# c1101_atmega32u4.net
KiCad netlist of a schematic drawn in EAGLE
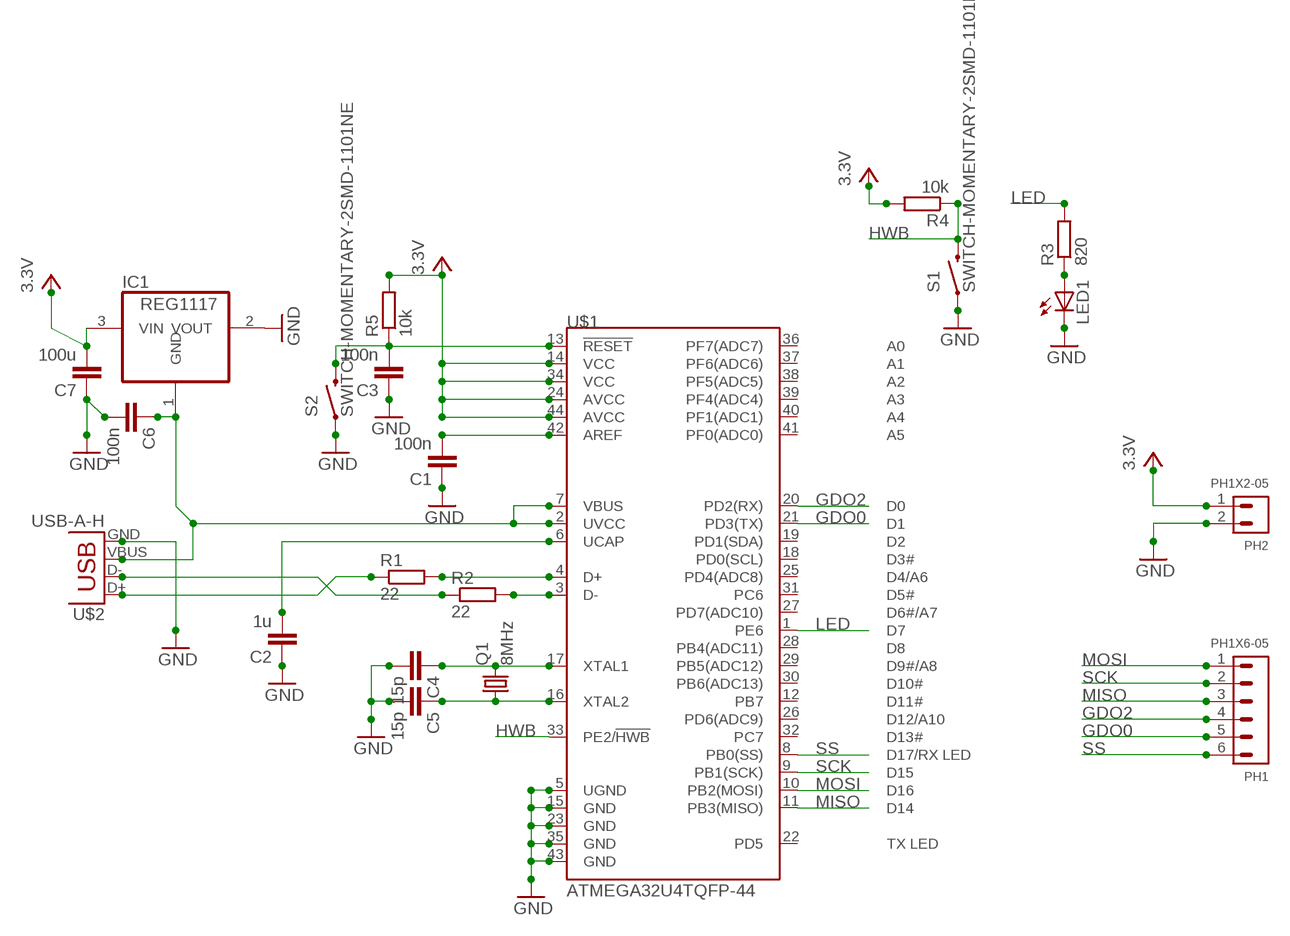
[diagram p0: schematic, sheet 1]

(export (version "E")
  (design (tool "Eeschema 10.0.6"))
  (components
    (comp (ref "C1")
      (value "100n")
      (footprint "eagle-import:C0805")
      (libsource (lib "eagle-import") (part "C-EUC0805"))
    )
    (comp (ref "C2")
      (value "1u")
      (footprint "eagle-import:C0805")
      (libsource (lib "eagle-import") (part "C-EUC0805"))
    )
    (comp (ref "C3")
      (value "100n")
      (footprint "eagle-import:C0805")
      (libsource (lib "eagle-import") (part "C-EUC0805"))
    )
    (comp (ref "C4")
      (value "15p")
      (footprint "eagle-import:C0805")
      (libsource (lib "eagle-import") (part "C-EUC0805"))
    )
    (comp (ref "C5")
      (value "15p")
      (footprint "eagle-import:C0805")
      (libsource (lib "eagle-import") (part "C-EUC0805"))
    )
    (comp (ref "C6")
      (value "100n")
      (footprint "eagle-import:C0805")
      (libsource (lib "eagle-import") (part "C-EUC0805"))
    )
    (comp (ref "C7")
      (value "100u")
      (footprint "eagle-import:C0805")
      (libsource (lib "eagle-import") (part "C-EUC0805"))
    )
    (comp (ref "IC1")
      (value "REG1117")
      (footprint "eagle-import:SOT223")
      (libsource (lib "eagle-import") (part "REG1117"))
    )
    (comp (ref "LED1")
      (value "LEDCHIPLED_1206")
      (footprint "eagle-import:CHIPLED_1206")
      (libsource (lib "eagle-import") (part "LEDCHIPLED_1206"))
    )
    (comp (ref "PH1")
      (value "PH1X6-05")
      (footprint "eagle-import:PH005-1-6")
      (libsource (lib "eagle-import") (part "PH1X6-05"))
    )
    (comp (ref "PH2")
      (value "PH1X2-05")
      (footprint "eagle-import:PH005-1-2")
      (libsource (lib "eagle-import") (part "PH1X2-05"))
    )
    (comp (ref "Q1")
      (value "8MHz")
      (footprint "eagle-import:HC49_S")
      (libsource (lib "eagle-import") (part "CRYSTALHC49S"))
    )
    (comp (ref "R1")
      (value "22")
      (footprint "eagle-import:M0805")
      (libsource (lib "eagle-import") (part "R-EU_M0805"))
    )
    (comp (ref "R2")
      (value "22")
      (footprint "eagle-import:M0805")
      (libsource (lib "eagle-import") (part "R-EU_M0805"))
    )
    (comp (ref "R3")
      (value "820")
      (footprint "eagle-import:M0805")
      (libsource (lib "eagle-import") (part "R-EU_M0805"))
    )
    (comp (ref "R4")
      (value "10k")
      (footprint "eagle-import:M0805")
      (libsource (lib "eagle-import") (part "R-EU_M0805"))
    )
    (comp (ref "R5")
      (value "10k")
      (footprint "eagle-import:M0805")
      (libsource (lib "eagle-import") (part "R-EU_M0805"))
    )
    (comp (ref "S1")
      (value "SWITCH-MOMENTARY-2SMD-1101NE")
      (footprint "eagle-import:TACTILE-SWITCH-1101NE")
      (libsource (lib "eagle-import") (part "SWITCH-MOMENTARY-2SMD-1101NE"))
    )
    (comp (ref "S2")
      (value "SWITCH-MOMENTARY-2SMD-1101NE")
      (footprint "eagle-import:TACTILE-SWITCH-1101NE")
      (libsource (lib "eagle-import") (part "SWITCH-MOMENTARY-2SMD-1101NE"))
    )
    (comp (ref "U$1")
      (value "ATMEGA32U4TQFP-44")
      (footprint "eagle-import:TQFP44")
      (libsource (lib "eagle-import") (part "ATMEGA32U4TQFP-44"))
    )
    (comp (ref "U$2")
      (value "USB-A-H")
      (footprint "eagle-import:USB-A-H")
      (libsource (lib "eagle-import") (part "USB-A-H"))
    )
  )
  (nets
    (net (code "1") (name "/GDO0") (class "Default")
      (node (ref "PH1") (pin "5") (pinfunction "5_5") (pintype "bidirectional"))
      (node (ref "U$1") (pin "21") (pinfunction "PD3(TX)_21") (pintype "bidirectional"))
    )
    (net (code "2") (name "/GDO2") (class "Default")
      (node (ref "PH1") (pin "4") (pinfunction "4_4") (pintype "bidirectional"))
      (node (ref "U$1") (pin "20") (pinfunction "PD2(RX)_20") (pintype "bidirectional"))
    )
    (net (code "3") (name "/HWB") (class "Default")
      (node (ref "R4") (pin "1") (pinfunction "1_1") (pintype "passive"))
      (node (ref "S1") (pin "2") (pinfunction "2_2") (pintype "passive"))
      (node (ref "U$1") (pin "33") (pinfunction "PE2/~{HWB}_33") (pintype "bidirectional"))
    )
    (net (code "4") (name "/LED") (class "Default")
      (node (ref "R3") (pin "2") (pinfunction "2_2") (pintype "passive"))
      (node (ref "U$1") (pin "1") (pinfunction "PE6_1") (pintype "bidirectional"))
    )
    (net (code "5") (name "/MISO") (class "Default")
      (node (ref "PH1") (pin "3") (pinfunction "3_3") (pintype "bidirectional"))
      (node (ref "U$1") (pin "11") (pinfunction "PB3(MISO)_11") (pintype "bidirectional"))
    )
    (net (code "6") (name "/MOSI") (class "Default")
      (node (ref "PH1") (pin "1") (pinfunction "1_1") (pintype "bidirectional"))
      (node (ref "U$1") (pin "10") (pinfunction "PB2(MOSI)_10") (pintype "bidirectional"))
    )
    (net (code "7") (name "/SCK") (class "Default")
      (node (ref "PH1") (pin "2") (pinfunction "2_2") (pintype "bidirectional"))
      (node (ref "U$1") (pin "9") (pinfunction "PB1(SCK)_9") (pintype "bidirectional"))
    )
    (net (code "8") (name "/SS") (class "Default")
      (node (ref "PH1") (pin "6") (pinfunction "6_6") (pintype "bidirectional"))
      (node (ref "U$1") (pin "8") (pinfunction "PB0(SS)_8") (pintype "bidirectional"))
    )
    (net (code "9") (name "3.3V") (class "Default")
      (node (ref "C7") (pin "2") (pinfunction "2_2") (pintype "passive"))
      (node (ref "IC1") (pin "3") (pinfunction "VIN_3") (pintype "input"))
      (node (ref "PH2") (pin "1") (pinfunction "1_1") (pintype "bidirectional"))
      (node (ref "R4") (pin "2") (pinfunction "2_2") (pintype "passive"))
      (node (ref "R5") (pin "2") (pinfunction "2_2") (pintype "passive"))
      (node (ref "U$1") (pin "14") (pinfunction "VCC_14") (pintype "bidirectional"))
      (node (ref "U$1") (pin "24") (pinfunction "AVCC_24") (pintype "bidirectional"))
      (node (ref "U$1") (pin "34") (pinfunction "VCC_34") (pintype "bidirectional"))
      (node (ref "U$1") (pin "44") (pinfunction "AVCC_44") (pintype "bidirectional"))
    )
    (net (code "10") (name "GND") (class "Default")
      (node (ref "C1") (pin "1") (pinfunction "1_1") (pintype "passive"))
      (node (ref "C2") (pin "1") (pinfunction "1_1") (pintype "passive"))
      (node (ref "C3") (pin "1") (pinfunction "1_1") (pintype "passive"))
      (node (ref "C4") (pin "2") (pinfunction "2_2") (pintype "passive"))
      (node (ref "C5") (pin "2") (pinfunction "2_2") (pintype "passive"))
      (node (ref "C6") (pin "2") (pinfunction "2_2") (pintype "passive"))
      (node (ref "C7") (pin "1") (pinfunction "1_1") (pintype "passive"))
      (node (ref "IC1") (pin "2") (pinfunction "VOUT_2") (pintype "output"))
      (node (ref "LED1") (pin "C") (pinfunction "C_C") (pintype "passive"))
      (node (ref "PH2") (pin "2") (pinfunction "2_2") (pintype "bidirectional"))
      (node (ref "S1") (pin "1") (pinfunction "1_1") (pintype "passive"))
      (node (ref "S2") (pin "1") (pinfunction "1_1") (pintype "passive"))
      (node (ref "U$1") (pin "15") (pinfunction "GND_15") (pintype "bidirectional"))
      (node (ref "U$1") (pin "23") (pinfunction "GND_23") (pintype "bidirectional"))
      (node (ref "U$1") (pin "35") (pinfunction "GND_35") (pintype "bidirectional"))
      (node (ref "U$1") (pin "43") (pinfunction "GND_43") (pintype "bidirectional"))
      (node (ref "U$1") (pin "5") (pinfunction "UGND_5") (pintype "bidirectional"))
      (node (ref "U$2") (pin "GND") (pinfunction "GND_GND") (pintype "bidirectional"))
    )
    (net (code "11") (name "Net-(IC1-GND)") (class "Default")
      (node (ref "C6") (pin "1") (pinfunction "1_1") (pintype "passive"))
      (node (ref "IC1") (pin "1") (pinfunction "GND_1") (pintype "power_in"))
      (node (ref "U$1") (pin "2") (pinfunction "UVCC_2") (pintype "bidirectional"))
      (node (ref "U$1") (pin "7") (pinfunction "VBUS_7") (pintype "bidirectional"))
      (node (ref "U$2") (pin "VBUS") (pinfunction "VBUS_VBUS") (pintype "bidirectional"))
    )
    (net (code "12") (name "Net-(LED1-PadA)") (class "Default")
      (node (ref "LED1") (pin "A") (pinfunction "A_A") (pintype "passive"))
      (node (ref "R3") (pin "1") (pinfunction "1_1") (pintype "passive"))
    )
    (net (code "13") (name "Net-(R1-Pad1)") (class "Default")
      (node (ref "R1") (pin "1") (pinfunction "1_1") (pintype "passive"))
      (node (ref "U$2") (pin "D+") (pinfunction "D+_D+") (pintype "bidirectional"))
    )
    (net (code "14") (name "Net-(R2-Pad1)") (class "Default")
      (node (ref "R2") (pin "1") (pinfunction "1_1") (pintype "passive"))
      (node (ref "U$2") (pin "D-") (pinfunction "D-_D-") (pintype "bidirectional"))
    )
    (net (code "15") (name "Net-(U$1-AREF)") (class "Default")
      (node (ref "C1") (pin "2") (pinfunction "2_2") (pintype "passive"))
      (node (ref "U$1") (pin "42") (pinfunction "AREF_42") (pintype "bidirectional"))
    )
    (net (code "16") (name "Net-(U$1-D+)") (class "Default")
      (node (ref "R1") (pin "2") (pinfunction "2_2") (pintype "passive"))
      (node (ref "U$1") (pin "4") (pinfunction "D+_4") (pintype "bidirectional"))
    )
    (net (code "17") (name "Net-(U$1-D-)") (class "Default")
      (node (ref "R2") (pin "2") (pinfunction "2_2") (pintype "passive"))
      (node (ref "U$1") (pin "3") (pinfunction "D-_3") (pintype "bidirectional"))
    )
    (net (code "18") (name "Net-(U$1-UCAP)") (class "Default")
      (node (ref "C2") (pin "2") (pinfunction "2_2") (pintype "passive"))
      (node (ref "U$1") (pin "6") (pinfunction "UCAP_6") (pintype "bidirectional"))
    )
    (net (code "19") (name "Net-(U$1-XTAL1)") (class "Default")
      (node (ref "C4") (pin "1") (pinfunction "1_1") (pintype "passive"))
      (node (ref "Q1") (pin "2") (pinfunction "2_2") (pintype "passive"))
      (node (ref "U$1") (pin "17") (pinfunction "XTAL1_17") (pintype "bidirectional"))
    )
    (net (code "20") (name "Net-(U$1-XTAL2)") (class "Default")
      (node (ref "C5") (pin "1") (pinfunction "1_1") (pintype "passive"))
      (node (ref "Q1") (pin "1") (pinfunction "1_1") (pintype "passive"))
      (node (ref "U$1") (pin "16") (pinfunction "XTAL2_16") (pintype "bidirectional"))
    )
    (net (code "21") (name "Net-(U$1-~{RESET})") (class "Default")
      (node (ref "C3") (pin "2") (pinfunction "2_2") (pintype "passive"))
      (node (ref "R5") (pin "1") (pinfunction "1_1") (pintype "passive"))
      (node (ref "S2") (pin "2") (pinfunction "2_2") (pintype "passive"))
      (node (ref "U$1") (pin "13") (pinfunction "~{RESET}_13") (pintype "bidirectional"))
    )
    (net (code "22") (name "unconnected-(U$1-PB4(ADC11)-Pad28)") (class "Default")
      (node (ref "U$1") (pin "28") (pinfunction "PB4(ADC11)_28") (pintype "bidirectional"))
    )
    (net (code "23") (name "unconnected-(U$1-PB5(ADC12)-Pad29)") (class "Default")
      (node (ref "U$1") (pin "29") (pinfunction "PB5(ADC12)_29") (pintype "bidirectional"))
    )
    (net (code "24") (name "unconnected-(U$1-PB6(ADC13)-Pad30)") (class "Default")
      (node (ref "U$1") (pin "30") (pinfunction "PB6(ADC13)_30") (pintype "bidirectional"))
    )
    (net (code "25") (name "unconnected-(U$1-PB7-Pad12)") (class "Default")
      (node (ref "U$1") (pin "12") (pinfunction "PB7_12") (pintype "bidirectional"))
    )
    (net (code "26") (name "unconnected-(U$1-PC6-Pad31)") (class "Default")
      (node (ref "U$1") (pin "31") (pinfunction "PC6_31") (pintype "bidirectional"))
    )
    (net (code "27") (name "unconnected-(U$1-PC7-Pad32)") (class "Default")
      (node (ref "U$1") (pin "32") (pinfunction "PC7_32") (pintype "bidirectional"))
    )
    (net (code "28") (name "unconnected-(U$1-PD0(SCL)-Pad18)") (class "Default")
      (node (ref "U$1") (pin "18") (pinfunction "PD0(SCL)_18") (pintype "bidirectional"))
    )
    (net (code "29") (name "unconnected-(U$1-PD1(SDA)-Pad19)") (class "Default")
      (node (ref "U$1") (pin "19") (pinfunction "PD1(SDA)_19") (pintype "bidirectional"))
    )
    (net (code "30") (name "unconnected-(U$1-PD4(ADC8)-Pad25)") (class "Default")
      (node (ref "U$1") (pin "25") (pinfunction "PD4(ADC8)_25") (pintype "bidirectional"))
    )
    (net (code "31") (name "unconnected-(U$1-PD5-Pad22)") (class "Default")
      (node (ref "U$1") (pin "22") (pinfunction "PD5_22") (pintype "bidirectional"))
    )
    (net (code "32") (name "unconnected-(U$1-PD6(ADC9)-Pad26)") (class "Default")
      (node (ref "U$1") (pin "26") (pinfunction "PD6(ADC9)_26") (pintype "bidirectional"))
    )
    (net (code "33") (name "unconnected-(U$1-PD7(ADC10)-Pad27)") (class "Default")
      (node (ref "U$1") (pin "27") (pinfunction "PD7(ADC10)_27") (pintype "bidirectional"))
    )
    (net (code "34") (name "unconnected-(U$1-PF0(ADC0)-Pad41)") (class "Default")
      (node (ref "U$1") (pin "41") (pinfunction "PF0(ADC0)_41") (pintype "bidirectional"))
    )
    (net (code "35") (name "unconnected-(U$1-PF1(ADC1)-Pad40)") (class "Default")
      (node (ref "U$1") (pin "40") (pinfunction "PF1(ADC1)_40") (pintype "bidirectional"))
    )
    (net (code "36") (name "unconnected-(U$1-PF4(ADC4)-Pad39)") (class "Default")
      (node (ref "U$1") (pin "39") (pinfunction "PF4(ADC4)_39") (pintype "bidirectional"))
    )
    (net (code "37") (name "unconnected-(U$1-PF5(ADC5)-Pad38)") (class "Default")
      (node (ref "U$1") (pin "38") (pinfunction "PF5(ADC5)_38") (pintype "bidirectional"))
    )
    (net (code "38") (name "unconnected-(U$1-PF6(ADC6)-Pad37)") (class "Default")
      (node (ref "U$1") (pin "37") (pinfunction "PF6(ADC6)_37") (pintype "bidirectional"))
    )
    (net (code "39") (name "unconnected-(U$1-PF7(ADC7)-Pad36)") (class "Default")
      (node (ref "U$1") (pin "36") (pinfunction "PF7(ADC7)_36") (pintype "bidirectional"))
    )
  )
)
